# telemetry-phoenix.net
KiCad netlist of a schematic drawn in EAGLE
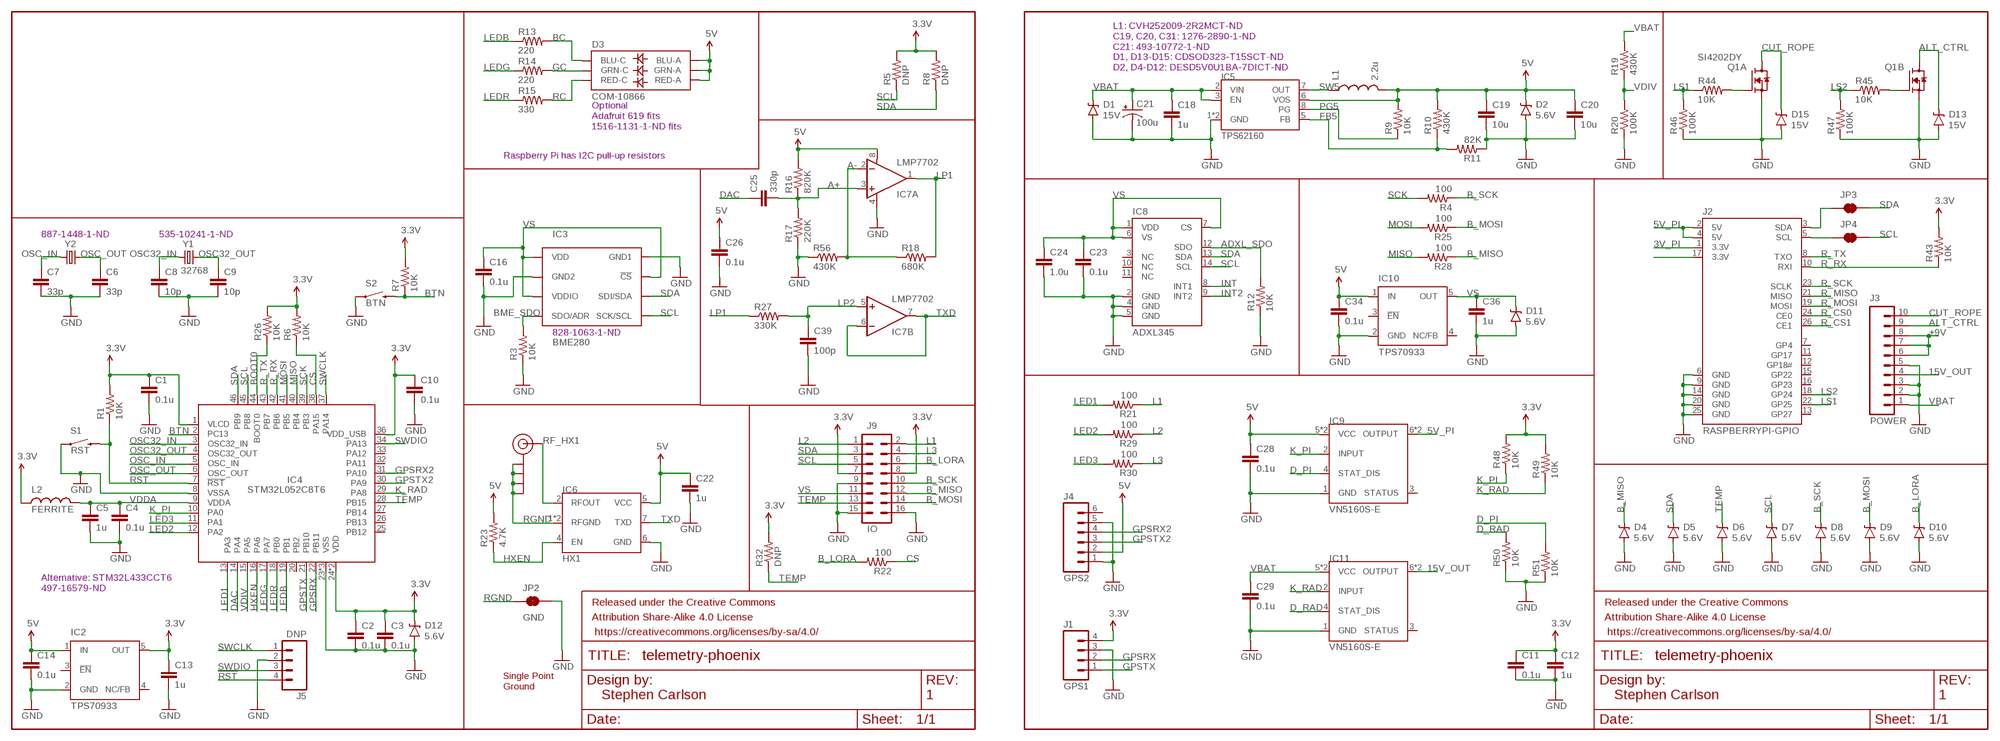
[diagram p0: schematic, sheet 1]

(export (version "E")
  (design (tool "Eeschema 10.0.6"))
  (components
    (comp (ref "C1")
      (value "0.1u")
      (footprint "eagle-import:0805")
      (libsource (lib "eagle-import") (part "CAP0805"))
    )
    (comp (ref "C2")
      (value "0.1u")
      (footprint "eagle-import:0805")
      (libsource (lib "eagle-import") (part "CAP0805"))
    )
    (comp (ref "C3")
      (value "0.1u")
      (footprint "eagle-import:0805")
      (libsource (lib "eagle-import") (part "CAP0805"))
    )
    (comp (ref "C4")
      (value "0.1u")
      (footprint "eagle-import:0805")
      (libsource (lib "eagle-import") (part "CAP0805"))
    )
    (comp (ref "C5")
      (value "1u")
      (footprint "eagle-import:0805")
      (libsource (lib "eagle-import") (part "CAP0805"))
    )
    (comp (ref "C6")
      (value "33p")
      (footprint "eagle-import:0805")
      (libsource (lib "eagle-import") (part "CAP0805"))
    )
    (comp (ref "C7")
      (value "33p")
      (footprint "eagle-import:0805")
      (libsource (lib "eagle-import") (part "CAP0805"))
    )
    (comp (ref "C8")
      (value "10p")
      (footprint "eagle-import:0805")
      (libsource (lib "eagle-import") (part "CAP0805"))
    )
    (comp (ref "C9")
      (value "10p")
      (footprint "eagle-import:0805")
      (libsource (lib "eagle-import") (part "CAP0805"))
    )
    (comp (ref "C10")
      (value "0.1u")
      (footprint "eagle-import:0805")
      (libsource (lib "eagle-import") (part "CAP0805"))
    )
    (comp (ref "C11")
      (value "0.1u")
      (footprint "eagle-import:0805")
      (libsource (lib "eagle-import") (part "CAP0805"))
    )
    (comp (ref "C12")
      (value "1u")
      (footprint "eagle-import:0805")
      (libsource (lib "eagle-import") (part "CAP0805"))
    )
    (comp (ref "C13")
      (value "1u")
      (footprint "eagle-import:0805")
      (libsource (lib "eagle-import") (part "CAP0805"))
    )
    (comp (ref "C14")
      (value "0.1u")
      (footprint "eagle-import:0805")
      (libsource (lib "eagle-import") (part "CAP0805"))
    )
    (comp (ref "C16")
      (value "0.1u")
      (footprint "eagle-import:0805")
      (libsource (lib "eagle-import") (part "CAP0805"))
    )
    (comp (ref "C18")
      (value "1u")
      (footprint "eagle-import:0805")
      (libsource (lib "eagle-import") (part "CAP0805"))
    )
    (comp (ref "C19")
      (value "10u")
      (footprint "eagle-import:0805")
      (libsource (lib "eagle-import") (part "CAP0805"))
    )
    (comp (ref "C20")
      (value "10u")
      (footprint "eagle-import:0805")
      (libsource (lib "eagle-import") (part "CAP0805"))
    )
    (comp (ref "C21")
      (value "100u")
      (footprint "eagle-import:PANASONIC_E")
      (libsource (lib "eagle-import") (part "CAP_POLE"))
    )
    (comp (ref "C22")
      (value "1u")
      (footprint "eagle-import:0805")
      (libsource (lib "eagle-import") (part "CAP0805"))
    )
    (comp (ref "C23")
      (value "0.1u")
      (footprint "eagle-import:0805")
      (libsource (lib "eagle-import") (part "CAP0805"))
    )
    (comp (ref "C24")
      (value "1.0u")
      (footprint "eagle-import:0805")
      (libsource (lib "eagle-import") (part "CAP0805"))
    )
    (comp (ref "C25")
      (value "330p")
      (footprint "eagle-import:0805")
      (libsource (lib "eagle-import") (part "CAP0805"))
    )
    (comp (ref "C26")
      (value "0.1u")
      (footprint "eagle-import:0805")
      (libsource (lib "eagle-import") (part "CAP0805"))
    )
    (comp (ref "C28")
      (value "0.1u")
      (footprint "eagle-import:0805")
      (libsource (lib "eagle-import") (part "CAP0805"))
    )
    (comp (ref "C29")
      (value "0.1u")
      (footprint "eagle-import:0805")
      (libsource (lib "eagle-import") (part "CAP0805"))
    )
    (comp (ref "C34")
      (value "0.1u")
      (footprint "eagle-import:0805")
      (libsource (lib "eagle-import") (part "CAP0805"))
    )
    (comp (ref "C36")
      (value "1u")
      (footprint "eagle-import:0805")
      (libsource (lib "eagle-import") (part "CAP0805"))
    )
    (comp (ref "C39")
      (value "100p")
      (footprint "eagle-import:0805")
      (libsource (lib "eagle-import") (part "CAP0805"))
    )
    (comp (ref "D1")
      (value "15V")
      (footprint "eagle-import:SOD-323")
      (libsource (lib "eagle-import") (part "DIODE-ZENER5.6V"))
    )
    (comp (ref "D2")
      (value "5.6V")
      (footprint "eagle-import:SOD-323")
      (libsource (lib "eagle-import") (part "DIODE-ZENER5.6V"))
    )
    (comp (ref "D3")
      (value "COM-10866")
      (footprint "eagle-import:LED-TRICOLOR-5050")
      (libsource (lib "eagle-import") (part "LED-TRICOLOR-5050NO_IC"))
    )
    (comp (ref "D4")
      (value "5.6V")
      (footprint "eagle-import:SOD-323")
      (libsource (lib "eagle-import") (part "DIODE-ZENER5.6V"))
    )
    (comp (ref "D5")
      (value "5.6V")
      (footprint "eagle-import:SOD-323")
      (libsource (lib "eagle-import") (part "DIODE-ZENER5.6V"))
    )
    (comp (ref "D6")
      (value "5.6V")
      (footprint "eagle-import:SOD-323")
      (libsource (lib "eagle-import") (part "DIODE-ZENER5.6V"))
    )
    (comp (ref "D7")
      (value "5.6V")
      (footprint "eagle-import:SOD-323")
      (libsource (lib "eagle-import") (part "DIODE-ZENER5.6V"))
    )
    (comp (ref "D8")
      (value "5.6V")
      (footprint "eagle-import:SOD-323")
      (libsource (lib "eagle-import") (part "DIODE-ZENER5.6V"))
    )
    (comp (ref "D9")
      (value "5.6V")
      (footprint "eagle-import:SOD-323")
      (libsource (lib "eagle-import") (part "DIODE-ZENER5.6V"))
    )
    (comp (ref "D10")
      (value "5.6V")
      (footprint "eagle-import:SOD-323")
      (libsource (lib "eagle-import") (part "DIODE-ZENER5.6V"))
    )
    (comp (ref "D11")
      (value "5.6V")
      (footprint "eagle-import:SOD-323")
      (libsource (lib "eagle-import") (part "DIODE-ZENER5.6V"))
    )
    (comp (ref "D12")
      (value "5.6V")
      (footprint "eagle-import:SOD-323")
      (libsource (lib "eagle-import") (part "DIODE-ZENER5.6V"))
    )
    (comp (ref "D13")
      (value "15V")
      (footprint "eagle-import:SOD-323")
      (libsource (lib "eagle-import") (part "DIODE-ZENER5.6V"))
    )
    (comp (ref "D15")
      (value "15V")
      (footprint "eagle-import:SOD-323")
      (libsource (lib "eagle-import") (part "DIODE-ZENER5.6V"))
    )
    (comp (ref "FRAME1")
      (value "FRAME-LETTERNO_PACKAGE")
      (footprint "eagle-import:DUMMY")
      (fields (field (name "DESIGNER") "Nobody"))
      (libsource (lib "eagle-import") (part "FRAME-LETTERNO_PACKAGE"))
    )
    (comp (ref "FRAME2")
      (value "FRAME-LETTERNO_PACKAGE")
      (footprint "eagle-import:DUMMY")
      (fields (field (name "DESIGNER") "Nobody"))
      (libsource (lib "eagle-import") (part "FRAME-LETTERNO_PACKAGE"))
    )
    (comp (ref "IC2")
      (value "TPS70933")
      (footprint "eagle-import:SOT23-DBV")
      (fields (field (name "MF") "TEXAS INSTRUMENTS") (field (name "MPN") "TPS77033DBVT"))
      (libsource (lib "eagle-import") (part "TPS77033"))
    )
    (comp (ref "IC3")
      (value "BME280")
      (footprint "eagle-import:BME280_LGA")
      (libsource (lib "eagle-import") (part "BME280"))
    )
    (comp (ref "IC4")
      (value "STM32L052C8T6")
      (footprint "eagle-import:TQFP48")
      (libsource (lib "eagle-import") (part "STM32L07C"))
    )
    (comp (ref "IC5")
      (value "TPS62160")
      (footprint "eagle-import:MSOP8")
      (libsource (lib "eagle-import") (part "TPS62160"))
    )
    (comp (ref "IC6")
      (value "HX1")
      (footprint "eagle-import:HX1")
      (libsource (lib "eagle-import") (part "HX1"))
    )
    (comp (ref "IC7")
      (value "LMP7702")
      (footprint "eagle-import:SO08")
      (libsource (lib "eagle-import") (part "OPAMP-DUALU"))
    )
    (comp (ref "IC8")
      (value "ADXL345")
      (footprint "eagle-import:LGA14")
      (libsource (lib "eagle-import") (part "ADXL345"))
    )
    (comp (ref "IC9")
      (value "VN5160S-E")
      (footprint "eagle-import:SO8")
      (libsource (lib "eagle-import") (part "VN5160S-E"))
    )
    (comp (ref "IC10")
      (value "TPS70933")
      (footprint "eagle-import:SOT23-DBV")
      (fields (field (name "MF") "TEXAS INSTRUMENTS") (field (name "MPN") "TPS77033DBVT"))
      (libsource (lib "eagle-import") (part "TPS77033"))
    )
    (comp (ref "IC11")
      (value "VN5160S-E")
      (footprint "eagle-import:SO8")
      (libsource (lib "eagle-import") (part "VN5160S-E"))
    )
    (comp (ref "J1")
      (value "GPS1")
      (footprint "eagle-import:1X04")
      (libsource (lib "eagle-import") (part "M04PTH"))
    )
    (comp (ref "J2")
      (value "RASPBERRYPI-GPIO")
      (footprint "eagle-import:2X13-PI")
      (libsource (lib "eagle-import") (part "RASPBERRYPI-GPIO"))
    )
    (comp (ref "J3")
      (value "POWER")
      (footprint "eagle-import:1X10_SCREW")
      (libsource (lib "eagle-import") (part "1X10"))
    )
    (comp (ref "J4")
      (value "GPS2")
      (footprint "eagle-import:1X06-1MM")
      (libsource (lib "eagle-import") (part "M06SMD-1MM"))
    )
    (comp (ref "J5")
      (value "DNP")
      (footprint "eagle-import:1X04_LOCK")
      (libsource (lib "eagle-import") (part "M04LOCK"))
    )
    (comp (ref "J6")
      (value "SMA_EDGE")
      (footprint "eagle-import:SMA-EDGE")
      (libsource (lib "eagle-import") (part "SMA_EDGE"))
    )
    (comp (ref "J9")
      (value "IO")
      (footprint "eagle-import:2X8")
      (libsource (lib "eagle-import") (part "M08X2"))
    )
    (comp (ref "JP2")
      (value "GND")
      (footprint "eagle-import:PAD-JUMPER-2-NC_BY_TRACE_YES_SILK")
      (libsource (lib "eagle-import") (part "JUMPER-PAD-2-NC_BY_TRACE"))
    )
    (comp (ref "JP3")
      (value "SDA")
      (footprint "eagle-import:PAD-JUMPER-2-NC_BY_TRACE_YES_SILK")
      (libsource (lib "eagle-import") (part "JUMPER-PAD-2-NC_BY_TRACE"))
    )
    (comp (ref "JP4")
      (value "SCL")
      (footprint "eagle-import:PAD-JUMPER-2-NC_BY_TRACE_YES_SILK")
      (libsource (lib "eagle-import") (part "JUMPER-PAD-2-NC_BY_TRACE"))
    )
    (comp (ref "L1")
      (value "2.2u")
      (footprint "eagle-import:1008")
      (libsource (lib "eagle-import") (part "INDUCTOR1008"))
    )
    (comp (ref "L2")
      (value "FERRITE")
      (footprint "eagle-import:1206")
      (libsource (lib "eagle-import") (part "INDUCTOR1206"))
    )
    (comp (ref "Q1")
      (value "SI4202DY")
      (footprint "eagle-import:SO8")
      (libsource (lib "eagle-import") (part "SI4202DY"))
    )
    (comp (ref "R1")
      (value "10K")
      (footprint "eagle-import:0805")
      (libsource (lib "eagle-import") (part "RESISTOR0805-RES"))
    )
    (comp (ref "R3")
      (value "10K")
      (footprint "eagle-import:0805")
      (libsource (lib "eagle-import") (part "RESISTOR0805-RES"))
    )
    (comp (ref "R4")
      (value "100")
      (footprint "eagle-import:0805")
      (libsource (lib "eagle-import") (part "RESISTOR0805-RES"))
    )
    (comp (ref "R5")
      (value "DNP")
      (footprint "eagle-import:0805")
      (libsource (lib "eagle-import") (part "RESISTOR0805-RES"))
    )
    (comp (ref "R6")
      (value "10K")
      (footprint "eagle-import:0805")
      (libsource (lib "eagle-import") (part "RESISTOR0805-RES"))
    )
    (comp (ref "R7")
      (value "10K")
      (footprint "eagle-import:0805")
      (libsource (lib "eagle-import") (part "RESISTOR0805-RES"))
    )
    (comp (ref "R8")
      (value "DNP")
      (footprint "eagle-import:0805")
      (libsource (lib "eagle-import") (part "RESISTOR0805-RES"))
    )
    (comp (ref "R9")
      (value "10K")
      (footprint "eagle-import:0805")
      (libsource (lib "eagle-import") (part "RESISTOR0805-RES"))
    )
    (comp (ref "R10")
      (value "430K")
      (footprint "eagle-import:0805")
      (libsource (lib "eagle-import") (part "RESISTOR0805-RES"))
    )
    (comp (ref "R11")
      (value "82K")
      (footprint "eagle-import:0805")
      (libsource (lib "eagle-import") (part "RESISTOR0805-RES"))
    )
    (comp (ref "R12")
      (value "10K")
      (footprint "eagle-import:0805")
      (libsource (lib "eagle-import") (part "RESISTOR0805-RES"))
    )
    (comp (ref "R13")
      (value "220")
      (footprint "eagle-import:0805")
      (libsource (lib "eagle-import") (part "RESISTOR0805-RES"))
    )
    (comp (ref "R14")
      (value "220")
      (footprint "eagle-import:0805")
      (libsource (lib "eagle-import") (part "RESISTOR0805-RES"))
    )
    (comp (ref "R15")
      (value "330")
      (footprint "eagle-import:0805")
      (libsource (lib "eagle-import") (part "RESISTOR0805-RES"))
    )
    (comp (ref "R16")
      (value "820K")
      (footprint "eagle-import:0805")
      (libsource (lib "eagle-import") (part "RESISTOR0805-RES"))
    )
    (comp (ref "R17")
      (value "220K")
      (footprint "eagle-import:0805")
      (libsource (lib "eagle-import") (part "RESISTOR0805-RES"))
    )
    (comp (ref "R18")
      (value "680K")
      (footprint "eagle-import:0805")
      (libsource (lib "eagle-import") (part "RESISTOR0805-RES"))
    )
    (comp (ref "R19")
      (value "430K")
      (footprint "eagle-import:0805")
      (libsource (lib "eagle-import") (part "RESISTOR0805-RES"))
    )
    (comp (ref "R20")
      (value "100K")
      (footprint "eagle-import:0805")
      (libsource (lib "eagle-import") (part "RESISTOR0805-RES"))
    )
    (comp (ref "R21")
      (value "100")
      (footprint "eagle-import:0805")
      (libsource (lib "eagle-import") (part "RESISTOR0805-RES"))
    )
    (comp (ref "R22")
      (value "100")
      (footprint "eagle-import:0805")
      (libsource (lib "eagle-import") (part "RESISTOR0805-RES"))
    )
    (comp (ref "R23")
      (value "4.7K")
      (footprint "eagle-import:0805")
      (libsource (lib "eagle-import") (part "RESISTOR0805-RES"))
    )
    (comp (ref "R25")
      (value "100")
      (footprint "eagle-import:0805")
      (libsource (lib "eagle-import") (part "RESISTOR0805-RES"))
    )
    (comp (ref "R26")
      (value "10K")
      (footprint "eagle-import:0805")
      (libsource (lib "eagle-import") (part "RESISTOR0805-RES"))
    )
    (comp (ref "R27")
      (value "330K")
      (footprint "eagle-import:0805")
      (libsource (lib "eagle-import") (part "RESISTOR0805-RES"))
    )
    (comp (ref "R28")
      (value "100")
      (footprint "eagle-import:0805")
      (libsource (lib "eagle-import") (part "RESISTOR0805-RES"))
    )
    (comp (ref "R29")
      (value "100")
      (footprint "eagle-import:0805")
      (libsource (lib "eagle-import") (part "RESISTOR0805-RES"))
    )
    (comp (ref "R30")
      (value "100")
      (footprint "eagle-import:0805")
      (libsource (lib "eagle-import") (part "RESISTOR0805-RES"))
    )
    (comp (ref "R32")
      (value "DNP")
      (footprint "eagle-import:0805")
      (libsource (lib "eagle-import") (part "RESISTOR0805-RES"))
    )
    (comp (ref "R43")
      (value "10K")
      (footprint "eagle-import:0805")
      (libsource (lib "eagle-import") (part "RESISTOR0805-RES"))
    )
    (comp (ref "R44")
      (value "10K")
      (footprint "eagle-import:0805")
      (libsource (lib "eagle-import") (part "RESISTOR0805-RES"))
    )
    (comp (ref "R45")
      (value "10K")
      (footprint "eagle-import:0805")
      (libsource (lib "eagle-import") (part "RESISTOR0805-RES"))
    )
    (comp (ref "R46")
      (value "100K")
      (footprint "eagle-import:0805")
      (libsource (lib "eagle-import") (part "RESISTOR0805-RES"))
    )
    (comp (ref "R47")
      (value "100K")
      (footprint "eagle-import:0805")
      (libsource (lib "eagle-import") (part "RESISTOR0805-RES"))
    )
    (comp (ref "R48")
      (value "10K")
      (footprint "eagle-import:0805")
      (libsource (lib "eagle-import") (part "RESISTOR0805-RES"))
    )
    (comp (ref "R49")
      (value "10K")
      (footprint "eagle-import:0805")
      (libsource (lib "eagle-import") (part "RESISTOR0805-RES"))
    )
    (comp (ref "R50")
      (value "10K")
      (footprint "eagle-import:0805")
      (libsource (lib "eagle-import") (part "RESISTOR0805-RES"))
    )
    (comp (ref "R51")
      (value "10K")
      (footprint "eagle-import:0805")
      (libsource (lib "eagle-import") (part "RESISTOR0805-RES"))
    )
    (comp (ref "R56")
      (value "430K")
      (footprint "eagle-import:0805")
      (libsource (lib "eagle-import") (part "RESISTOR0805-RES"))
    )
    (comp (ref "S1")
      (value "RST")
      (footprint "eagle-import:TACTILE-PTH-THIN")
      (libsource (lib "eagle-import") (part "SWITCH"))
    )
    (comp (ref "S2")
      (value "BTN")
      (footprint "eagle-import:TACTILE-PTH-THIN")
      (libsource (lib "eagle-import") (part "SWITCH"))
    )
    (comp (ref "Y1")
      (value "32768")
      (footprint "eagle-import:ABS25")
      (libsource (lib "eagle-import") (part "CRYSTAL"))
    )
    (comp (ref "Y2")
      (value "8M")
      (footprint "eagle-import:CRYSTAL-TXC-7A")
      (libsource (lib "eagle-import") (part "CRYSTALTXC-7A"))
    )
  )
  (nets
    (net (code "1") (name "/+9V") (class "Default")
      (node (ref "J3") (pin "6") (pinfunction "6_6") (pintype "passive"))
      (node (ref "J3") (pin "7") (pinfunction "7_7") (pintype "passive"))
      (node (ref "J3") (pin "8") (pinfunction "8_8") (pintype "passive"))
    )
    (net (code "2") (name "/3V_PI") (class "Default")
      (node (ref "J2") (pin "1") (pinfunction "3.3V_1") (pintype "power_in"))
    )
    (net (code "3") (name "/5V_PI") (class "Default")
      (node (ref "IC9") (pin "6") (pinfunction "OUTPUT_6") (pintype "passive"))
      (node (ref "IC9") (pin "7") (pinfunction "OUTPUT_7") (pintype "passive"))
      (node (ref "J2") (pin "2") (pinfunction "5V_2") (pintype "power_in"))
      (node (ref "J2") (pin "4") (pinfunction "5V_4") (pintype "power_in"))
    )
    (net (code "4") (name "/15V_OUT") (class "Default")
      (node (ref "IC11") (pin "6") (pinfunction "OUTPUT_6") (pintype "passive"))
      (node (ref "IC11") (pin "7") (pinfunction "OUTPUT_7") (pintype "passive"))
      (node (ref "J3") (pin "4") (pinfunction "4_4") (pintype "passive"))
    )
    (net (code "5") (name "/A+") (class "Default")
      (node (ref "C25") (pin "2") (pinfunction "2_2") (pintype "passive"))
      (node (ref "IC7") (pin "3") (pinfunction "+IN_3") (pintype "input"))
      (node (ref "R16") (pin "1") (pinfunction "1_1") (pintype "passive"))
      (node (ref "R17") (pin "2") (pinfunction "2_2") (pintype "passive"))
    )
    (net (code "6") (name "/A-") (class "Default")
      (node (ref "IC7") (pin "2") (pinfunction "-IN_2") (pintype "input"))
      (node (ref "R18") (pin "1") (pinfunction "1_1") (pintype "passive"))
      (node (ref "R56") (pin "2") (pinfunction "2_2") (pintype "passive"))
    )
    (net (code "7") (name "/ADXL_SDO") (class "Default")
      (node (ref "IC8") (pin "12") (pinfunction "SDO_12") (pintype "bidirectional"))
      (node (ref "R12") (pin "2") (pinfunction "2_2") (pintype "passive"))
    )
    (net (code "8") (name "/ALT_CTRL") (class "Default")
      (node (ref "D13") (pin "C") (pinfunction "C_C") (pintype "passive"))
      (node (ref "J3") (pin "9") (pinfunction "9_9") (pintype "passive"))
      (node (ref "Q1") (pin "5") (pinfunction "D_5") (pintype "passive"))
      (node (ref "Q1") (pin "6") (pinfunction "D_6") (pintype "passive"))
    )
    (net (code "9") (name "/BC") (class "Default")
      (node (ref "D3") (pin "4") (pinfunction "BLU-C_4") (pintype "bidirectional"))
      (node (ref "R13") (pin "2") (pinfunction "2_2") (pintype "passive"))
    )
    (net (code "10") (name "/BME_SDO") (class "Default")
      (node (ref "IC3") (pin "P$5") (pinfunction "SDO/ADR_P$5") (pintype "bidirectional"))
      (node (ref "R3") (pin "2") (pinfunction "2_2") (pintype "passive"))
    )
    (net (code "11") (name "/BOOT0") (class "Default")
      (node (ref "IC4") (pin "44") (pinfunction "BOOT0_44") (pintype "input"))
      (node (ref "R26") (pin "1") (pinfunction "1_1") (pintype "passive"))
    )
    (net (code "12") (name "/BTN") (class "Default")
      (node (ref "IC4") (pin "2") (pinfunction "PC13_2") (pintype "bidirectional"))
      (node (ref "R7") (pin "1") (pinfunction "1_1") (pintype "passive"))
      (node (ref "S2") (pin "2") (pinfunction "2_2") (pintype "passive"))
    )
    (net (code "13") (name "/B_LORA") (class "Default")
      (node (ref "D10") (pin "C") (pinfunction "C_C") (pintype "passive"))
      (node (ref "J9") (pin "6") (pinfunction "6_6") (pintype "passive"))
      (node (ref "R22") (pin "2") (pinfunction "2_2") (pintype "passive"))
    )
    (net (code "14") (name "/B_MISO") (class "Default")
      (node (ref "D4") (pin "C") (pinfunction "C_C") (pintype "passive"))
      (node (ref "J9") (pin "12") (pinfunction "12_12") (pintype "passive"))
      (node (ref "R28") (pin "1") (pinfunction "1_1") (pintype "passive"))
    )
    (net (code "15") (name "/B_MOSI") (class "Default")
      (node (ref "D9") (pin "C") (pinfunction "C_C") (pintype "passive"))
      (node (ref "J9") (pin "14") (pinfunction "14_14") (pintype "passive"))
      (node (ref "R25") (pin "1") (pinfunction "1_1") (pintype "passive"))
    )
    (net (code "16") (name "/B_SCK") (class "Default")
      (node (ref "D8") (pin "C") (pinfunction "C_C") (pintype "passive"))
      (node (ref "J9") (pin "10") (pinfunction "10_10") (pintype "passive"))
      (node (ref "R4") (pin "1") (pinfunction "1_1") (pintype "passive"))
    )
    (net (code "17") (name "/CS") (class "Default")
      (node (ref "IC4") (pin "38") (pinfunction "PA15_38") (pintype "bidirectional"))
      (node (ref "R22") (pin "1") (pinfunction "1_1") (pintype "passive"))
      (node (ref "R6") (pin "1") (pinfunction "1_1") (pintype "passive"))
    )
    (net (code "18") (name "/CUT_ROPE") (class "Default")
      (node (ref "D15") (pin "C") (pinfunction "C_C") (pintype "passive"))
      (node (ref "J3") (pin "10") (pinfunction "10_10") (pintype "passive"))
      (node (ref "Q1") (pin "7") (pinfunction "D_7") (pintype "passive"))
      (node (ref "Q1") (pin "8") (pinfunction "D_8") (pintype "passive"))
    )
    (net (code "19") (name "/DAC") (class "Default")
      (node (ref "C25") (pin "1") (pinfunction "1_1") (pintype "passive"))
      (node (ref "IC4") (pin "14") (pinfunction "PA4_14") (pintype "bidirectional"))
    )
    (net (code "20") (name "/D_PI") (class "Default")
      (node (ref "IC9") (pin "4") (pinfunction "STAT_DIS_4") (pintype "input"))
      (node (ref "R51") (pin "2") (pinfunction "2_2") (pintype "passive"))
    )
    (net (code "21") (name "/D_RAD") (class "Default")
      (node (ref "IC11") (pin "4") (pinfunction "STAT_DIS_4") (pintype "input"))
      (node (ref "R50") (pin "2") (pinfunction "2_2") (pintype "passive"))
    )
    (net (code "22") (name "/FB5") (class "Default")
      (node (ref "IC5") (pin "5") (pinfunction "FB_5") (pintype "input"))
      (node (ref "R10") (pin "1") (pinfunction "1_1") (pintype "passive"))
      (node (ref "R11") (pin "2") (pinfunction "2_2") (pintype "passive"))
    )
    (net (code "23") (name "/GC") (class "Default")
      (node (ref "D3") (pin "6") (pinfunction "GRN-C_6") (pintype "bidirectional"))
      (node (ref "R14") (pin "2") (pinfunction "2_2") (pintype "passive"))
    )
    (net (code "24") (name "/GPSRX") (class "Default")
      (node (ref "IC4") (pin "22") (pinfunction "PB11_22") (pintype "bidirectional"))
      (node (ref "J1") (pin "2") (pinfunction "2_2") (pintype "passive"))
    )
    (net (code "25") (name "/GPSRX2") (class "Default")
      (node (ref "IC4") (pin "31") (pinfunction "PA10_31") (pintype "bidirectional"))
      (node (ref "J4") (pin "4") (pinfunction "4_4") (pintype "passive"))
    )
    (net (code "26") (name "/GPSTX") (class "Default")
      (node (ref "IC4") (pin "21") (pinfunction "PB10_21") (pintype "bidirectional"))
      (node (ref "J1") (pin "1") (pinfunction "1_1") (pintype "passive"))
    )
    (net (code "27") (name "/GPSTX2") (class "Default")
      (node (ref "IC4") (pin "30") (pinfunction "PA9_30") (pintype "bidirectional"))
      (node (ref "J4") (pin "3") (pinfunction "3_3") (pintype "passive"))
    )
    (net (code "28") (name "/HXEN") (class "Default")
      (node (ref "IC4") (pin "16") (pinfunction "PA6_16") (pintype "bidirectional"))
      (node (ref "IC6") (pin "4") (pinfunction "EN_4") (pintype "input"))
      (node (ref "R23") (pin "1") (pinfunction "1_1") (pintype "passive"))
    )
    (net (code "29") (name "/INT") (class "Default")
      (node (ref "IC8") (pin "8") (pinfunction "INT1_8") (pintype "bidirectional"))
    )
    (net (code "30") (name "/INT2") (class "Default")
      (node (ref "IC8") (pin "9") (pinfunction "INT2_9") (pintype "bidirectional"))
    )
    (net (code "31") (name "/K_PI") (class "Default")
      (node (ref "IC4") (pin "10") (pinfunction "PA0_10") (pintype "bidirectional"))
      (node (ref "IC9") (pin "2") (pinfunction "INPUT_2") (pintype "input"))
      (node (ref "R48") (pin "1") (pinfunction "1_1") (pintype "passive"))
    )
    (net (code "32") (name "/K_RAD") (class "Default")
      (node (ref "IC11") (pin "2") (pinfunction "INPUT_2") (pintype "input"))
      (node (ref "IC4") (pin "29") (pinfunction "PA8_29") (pintype "bidirectional"))
      (node (ref "R49") (pin "1") (pinfunction "1_1") (pintype "passive"))
    )
    (net (code "33") (name "/L1") (class "Default")
      (node (ref "J9") (pin "2") (pinfunction "2_2") (pintype "passive"))
      (node (ref "R21") (pin "1") (pinfunction "1_1") (pintype "passive"))
    )
    (net (code "34") (name "/L2") (class "Default")
      (node (ref "J9") (pin "1") (pinfunction "1_1") (pintype "passive"))
      (node (ref "R29") (pin "1") (pinfunction "1_1") (pintype "passive"))
    )
    (net (code "35") (name "/L3") (class "Default")
      (node (ref "J9") (pin "4") (pinfunction "4_4") (pintype "passive"))
      (node (ref "R30") (pin "1") (pinfunction "1_1") (pintype "passive"))
    )
    (net (code "36") (name "/LED1") (class "Default")
      (node (ref "IC4") (pin "13") (pinfunction "PA3_13") (pintype "bidirectional"))
      (node (ref "R21") (pin "2") (pinfunction "2_2") (pintype "passive"))
    )
    (net (code "37") (name "/LED2") (class "Default")
      (node (ref "IC4") (pin "12") (pinfunction "PA2_12") (pintype "bidirectional"))
      (node (ref "R29") (pin "2") (pinfunction "2_2") (pintype "passive"))
    )
    (net (code "38") (name "/LED3") (class "Default")
      (node (ref "IC4") (pin "11") (pinfunction "PA1_11") (pintype "bidirectional"))
      (node (ref "R30") (pin "2") (pinfunction "2_2") (pintype "passive"))
    )
    (net (code "39") (name "/LEDB") (class "Default")
      (node (ref "IC4") (pin "19") (pinfunction "PB1_19") (pintype "bidirectional"))
      (node (ref "R13") (pin "1") (pinfunction "1_1") (pintype "passive"))
    )
    (net (code "40") (name "/LEDG") (class "Default")
      (node (ref "IC4") (pin "17") (pinfunction "PA7_17") (pintype "bidirectional"))
      (node (ref "R14") (pin "1") (pinfunction "1_1") (pintype "passive"))
    )
    (net (code "41") (name "/LEDR") (class "Default")
      (node (ref "IC4") (pin "18") (pinfunction "PB0_18") (pintype "bidirectional"))
      (node (ref "R15") (pin "1") (pinfunction "1_1") (pintype "passive"))
    )
    (net (code "42") (name "/LP1") (class "Default")
      (node (ref "IC7") (pin "1") (pinfunction "OUT_1") (pintype "output"))
      (node (ref "R18") (pin "2") (pinfunction "2_2") (pintype "passive"))
      (node (ref "R27") (pin "1") (pinfunction "1_1") (pintype "passive"))
    )
    (net (code "43") (name "/LP2") (class "Default")
      (node (ref "C39") (pin "1") (pinfunction "1_1") (pintype "passive"))
      (node (ref "IC7") (pin "5") (pinfunction "+IN_5") (pintype "input"))
      (node (ref "R27") (pin "2") (pinfunction "2_2") (pintype "passive"))
    )
    (net (code "44") (name "/LS1") (class "Default")
      (node (ref "J2") (pin "22") (pinfunction "GP25_22") (pintype "bidirectional"))
      (node (ref "R44") (pin "1") (pinfunction "1_1") (pintype "passive"))
      (node (ref "R46") (pin "2") (pinfunction "2_2") (pintype "passive"))
    )
    (net (code "45") (name "/LS2") (class "Default")
      (node (ref "J2") (pin "18") (pinfunction "GP24_18") (pintype "bidirectional"))
      (node (ref "R45") (pin "1") (pinfunction "1_1") (pintype "passive"))
      (node (ref "R47") (pin "2") (pinfunction "2_2") (pintype "passive"))
    )
    (net (code "46") (name "/MISO") (class "Default")
      (node (ref "IC4") (pin "40") (pinfunction "PB4_40") (pintype "bidirectional"))
      (node (ref "R28") (pin "2") (pinfunction "2_2") (pintype "passive"))
    )
    (net (code "47") (name "/MOSI") (class "Default")
      (node (ref "IC4") (pin "41") (pinfunction "PB5_41") (pintype "bidirectional"))
      (node (ref "R25") (pin "2") (pinfunction "2_2") (pintype "passive"))
    )
    (net (code "48") (name "/OSC32_IN") (class "Default")
      (node (ref "C8") (pin "1") (pinfunction "1_1") (pintype "passive"))
      (node (ref "IC4") (pin "3") (pinfunction "OSC32_IN_3") (pintype "bidirectional"))
      (node (ref "Y1") (pin "1") (pinfunction "1_1") (pintype "passive"))
    )
    (net (code "49") (name "/OSC32_OUT") (class "Default")
      (node (ref "C9") (pin "1") (pinfunction "1_1") (pintype "passive"))
      (node (ref "IC4") (pin "4") (pinfunction "OSC32_OUT_4") (pintype "bidirectional"))
      (node (ref "Y1") (pin "4") (pinfunction "2_4") (pintype "passive"))
    )
    (net (code "50") (name "/OSC_IN") (class "Default")
      (node (ref "C7") (pin "1") (pinfunction "1_1") (pintype "passive"))
      (node (ref "IC4") (pin "5") (pinfunction "OSC_IN_5") (pintype "bidirectional"))
      (node (ref "Y2") (pin "P$1") (pinfunction "1_P$1") (pintype "passive"))
    )
    (net (code "51") (name "/OSC_OUT") (class "Default")
      (node (ref "C6") (pin "1") (pinfunction "1_1") (pintype "passive"))
      (node (ref "IC4") (pin "6") (pinfunction "OSC_OUT_6") (pintype "bidirectional"))
      (node (ref "Y2") (pin "P$2") (pinfunction "2_P$2") (pintype "passive"))
    )
    (net (code "52") (name "/PG5") (class "Default")
      (node (ref "IC5") (pin "8") (pinfunction "PG_8") (pintype "open_collector"))
      (node (ref "R9") (pin "1") (pinfunction "1_1") (pintype "passive"))
    )
    (net (code "53") (name "/RC") (class "Default")
      (node (ref "D3") (pin "5") (pinfunction "RED-C_5") (pintype "bidirectional"))
      (node (ref "R15") (pin "2") (pinfunction "2_2") (pintype "passive"))
    )
    (net (code "54") (name "/RF_HX1") (class "Default")
      (node (ref "IC6") (pin "2") (pinfunction "RFOUT_2") (pintype "output"))
      (node (ref "J6") (pin "SIG") (pinfunction "SIGNAL_SIG") (pintype "bidirectional"))
    )
    (net (code "55") (name "/RGND") (class "Default")
      (node (ref "IC6") (pin "1") (pinfunction "RFGND_1") (pintype "power_in"))
      (node (ref "IC6") (pin "3") (pinfunction "RFGND_3") (pintype "power_in"))
      (node (ref "J6") (pin "GND@0") (pinfunction "GND_GND@0") (pintype "bidirectional"))
      (node (ref "J6") (pin "GND@1") (pinfunction "GND_GND@1") (pintype "bidirectional"))
      (node (ref "J6") (pin "GND@2") (pinfunction "GND_GND@2") (pintype "bidirectional"))
      (node (ref "J6") (pin "GND@3") (pinfunction "GND_GND@3") (pintype "bidirectional"))
      (node (ref "JP2") (pin "1") (pinfunction "1_1") (pintype "passive"))
    )
    (net (code "56") (name "/R_CS0") (class "Default")
      (node (ref "J2") (pin "24") (pinfunction "CE0_24") (pintype "output"))
    )
    (net (code "57") (name "/R_CS1") (class "Default")
      (node (ref "J2") (pin "26") (pinfunction "CE1_26") (pintype "output"))
    )
    (net (code "58") (name "/R_MISO") (class "Default")
      (node (ref "J2") (pin "21") (pinfunction "MISO_21") (pintype "input"))
    )
    (net (code "59") (name "/R_MOSI") (class "Default")
      (node (ref "J2") (pin "19") (pinfunction "MOSI_19") (pintype "output"))
    )
    (net (code "60") (name "/R_RX") (class "Default")
      (node (ref "IC4") (pin "42") (pinfunction "PB6_42") (pintype "bidirectional"))
      (node (ref "J2") (pin "10") (pinfunction "RXI_10") (pintype "input"))
      (node (ref "R43") (pin "1") (pinfunction "1_1") (pintype "passive"))
    )
    (net (code "61") (name "/R_SCK") (class "Default")
      (node (ref "J2") (pin "23") (pinfunction "SCLK_23") (pintype "output"))
    )
    (net (code "62") (name "/R_TX") (class "Default")
      (node (ref "IC4") (pin "43") (pinfunction "PB7_43") (pintype "bidirectional"))
      (node (ref "J2") (pin "8") (pinfunction "TXO_8") (pintype "output"))
    )
    (net (code "63") (name "/SCK") (class "Default")
      (node (ref "IC4") (pin "39") (pinfunction "PB3_39") (pintype "bidirectional"))
      (node (ref "R4") (pin "2") (pinfunction "2_2") (pintype "passive"))
    )
    (net (code "64") (name "/SCL") (class "Default")
      (node (ref "D7") (pin "C") (pinfunction "C_C") (pintype "passive"))
      (node (ref "IC3") (pin "P$4") (pinfunction "SCK/SCL_P$4") (pintype "bidirectional"))
      (node (ref "IC4") (pin "45") (pinfunction "PB8_45") (pintype "bidirectional"))
      (node (ref "IC8") (pin "14") (pinfunction "SCL_14") (pintype "bidirectional"))
      (node (ref "J9") (pin "5") (pinfunction "5_5") (pintype "passive"))
      (node (ref "JP4") (pin "2") (pinfunction "2_2") (pintype "passive"))
      (node (ref "R5") (pin "1") (pinfunction "1_1") (pintype "passive"))
    )
    (net (code "65") (name "/SDA") (class "Default")
      (node (ref "D5") (pin "C") (pinfunction "C_C") (pintype "passive"))
      (node (ref "IC3") (pin "P$3") (pinfunction "SDI/SDA_P$3") (pintype "bidirectional"))
      (node (ref "IC4") (pin "46") (pinfunction "PB9_46") (pintype "bidirectional"))
      (node (ref "IC8") (pin "13") (pinfunction "SDA_13") (pintype "bidirectional"))
      (node (ref "J9") (pin "3") (pinfunction "3_3") (pintype "passive"))
      (node (ref "JP3") (pin "2") (pinfunction "2_2") (pintype "passive"))
      (node (ref "R8") (pin "1") (pinfunction "1_1") (pintype "passive"))
    )
    (net (code "66") (name "/SW5") (class "Default")
      (node (ref "IC5") (pin "7") (pinfunction "OUT_7") (pintype "output"))
      (node (ref "L1") (pin "1") (pinfunction "1_1") (pintype "passive"))
    )
    (net (code "67") (name "/SWCLK") (class "Default")
      (node (ref "IC4") (pin "37") (pinfunction "PA14_37") (pintype "bidirectional"))
      (node (ref "J5") (pin "1") (pinfunction "1_1") (pintype "passive"))
    )
    (net (code "68") (name "/SWDIO") (class "Default")
      (node (ref "IC4") (pin "34") (pinfunction "PA13_34") (pintype "bidirectional"))
      (node (ref "J5") (pin "3") (pinfunction "3_3") (pintype "passive"))
    )
    (net (code "69") (name "/TEMP") (class "Default")
      (node (ref "D6") (pin "C") (pinfunction "C_C") (pintype "passive"))
      (node (ref "IC4") (pin "28") (pinfunction "PB15_28") (pintype "bidirectional"))
      (node (ref "J9") (pin "13") (pinfunction "13_13") (pintype "passive"))
      (node (ref "R32") (pin "1") (pinfunction "1_1") (pintype "passive"))
    )
    (net (code "70") (name "/TXD") (class "Default")
      (node (ref "IC6") (pin "7") (pinfunction "TXD_7") (pintype "input"))
      (node (ref "IC7") (pin "6") (pinfunction "-IN_6") (pintype "input"))
      (node (ref "IC7") (pin "7") (pinfunction "OUT_7") (pintype "output"))
    )
    (net (code "71") (name "/VBAT") (class "Default")
      (node (ref "C18") (pin "1") (pinfunction "1_1") (pintype "passive"))
      (node (ref "C21") (pin "+") (pinfunction "+_+") (pintype "passive"))
      (node (ref "C29") (pin "1") (pinfunction "1_1") (pintype "passive"))
      (node (ref "D1") (pin "C") (pinfunction "C_C") (pintype "passive"))
      (node (ref "IC11") (pin "5") (pinfunction "VCC_5") (pintype "power_in"))
      (node (ref "IC11") (pin "8") (pinfunction "VCC_8") (pintype "power_in"))
      (node (ref "IC5") (pin "2") (pinfunction "VIN_2") (pintype "power_in"))
      (node (ref "IC5") (pin "3") (pinfunction "EN_3") (pintype "input"))
      (node (ref "J3") (pin "1") (pinfunction "1_1") (pintype "passive"))
      (node (ref "R19") (pin "2") (pinfunction "2_2") (pintype "passive"))
    )
    (net (code "72") (name "/VDDA") (class "Default")
      (node (ref "C4") (pin "1") (pinfunction "1_1") (pintype "passive"))
      (node (ref "C5") (pin "1") (pinfunction "1_1") (pintype "passive"))
      (node (ref "IC4") (pin "9") (pinfunction "VDDA_9") (pintype "power_in"))
      (node (ref "L2") (pin "2") (pinfunction "2_2") (pintype "passive"))
    )
    (net (code "73") (name "/VDIV") (class "Default")
      (node (ref "IC4") (pin "15") (pinfunction "PA5_15") (pintype "bidirectional"))
      (node (ref "R19") (pin "1") (pinfunction "1_1") (pintype "passive"))
      (node (ref "R20") (pin "2") (pinfunction "2_2") (pintype "passive"))
    )
    (net (code "74") (name "/VS") (class "Default")
      (node (ref "C16") (pin "1") (pinfunction "1_1") (pintype "passive"))
      (node (ref "C23") (pin "1") (pinfunction "1_1") (pintype "passive"))
      (node (ref "C24") (pin "1") (pinfunction "1_1") (pintype "passive"))
      (node (ref "C36") (pin "1") (pinfunction "1_1") (pintype "passive"))
      (node (ref "D11") (pin "C") (pinfunction "C_C") (pintype "passive"))
      (node (ref "IC10") (pin "5") (pinfunction "OUT_5") (pintype "passive"))
      (node (ref "IC3") (pin "P$2") (pinfunction "~{CS}_P$2") (pintype "bidirectional"))
      (node (ref "IC3") (pin "P$6") (pinfunction "VDDIO_P$6") (pintype "bidirectional"))
      (node (ref "IC3") (pin "P$8") (pinfunction "VDD_P$8") (pintype "bidirectional"))
      (node (ref "IC8") (pin "1") (pinfunction "VDD_1") (pintype "bidirectional"))
      (node (ref "IC8") (pin "6") (pinfunction "VS_6") (pintype "bidirectional"))
      (node (ref "IC8") (pin "7") (pinfunction "CS_7") (pintype "bidirectional"))
      (node (ref "J9") (pin "11") (pinfunction "11_11") (pintype "passive"))
    )
    (net (code "75") (name "/~{RST}") (class "Default")
      (node (ref "IC4") (pin "7") (pinfunction "~{RST}_7") (pintype "input"))
      (node (ref "J5") (pin "4") (pinfunction "4_4") (pintype "passive"))
      (node (ref "R1") (pin "1") (pinfunction "1_1") (pintype "passive"))
      (node (ref "S1") (pin "2") (pinfunction "2_2") (pintype "passive"))
    )
    (net (code "76") (name "3.3V") (class "Default")
      (node (ref "C1") (pin "1") (pinfunction "1_1") (pintype "passive"))
      (node (ref "C10") (pin "1") (pinfunction "1_1") (pintype "passive"))
      (node (ref "C11") (pin "1") (pinfunction "1_1") (pintype "passive"))
      (node (ref "C12") (pin "1") (pinfunction "1_1") (pintype "passive"))
      (node (ref "C13") (pin "1") (pinfunction "1_1") (pintype "passive"))
      (node (ref "C2") (pin "1") (pinfunction "1_1") (pintype "passive"))
      (node (ref "C3") (pin "1") (pinfunction "1_1") (pintype "passive"))
      (node (ref "D12") (pin "C") (pinfunction "C_C") (pintype "passive"))
      (node (ref "IC2") (pin "5") (pinfunction "OUT_5") (pintype "passive"))
      (node (ref "IC4") (pin "1") (pinfunction "VLCD_1") (pintype "power_in"))
      (node (ref "IC4") (pin "24") (pinfunction "VDD_24") (pintype "power_in"))
      (node (ref "IC4") (pin "36") (pinfunction "VDD_USB_36") (pintype "power_in"))
      (node (ref "IC4") (pin "48") (pinfunction "VDD_48") (pintype "power_in"))
      (node (ref "J1") (pin "4") (pinfunction "4_4") (pintype "passive"))
      (node (ref "J9") (pin "7") (pinfunction "7_7") (pintype "passive"))
      (node (ref "J9") (pin "8") (pinfunction "8_8") (pintype "passive"))
      (node (ref "L2") (pin "1") (pinfunction "1_1") (pintype "passive"))
      (node (ref "R1") (pin "2") (pinfunction "2_2") (pintype "passive"))
      (node (ref "R26") (pin "2") (pinfunction "2_2") (pintype "passive"))
      (node (ref "R32") (pin "2") (pinfunction "2_2") (pintype "passive"))
      (node (ref "R43") (pin "2") (pinfunction "2_2") (pintype "passive"))
      (node (ref "R48") (pin "2") (pinfunction "2_2") (pintype "passive"))
      (node (ref "R49") (pin "2") (pinfunction "2_2") (pintype "passive"))
      (node (ref "R5") (pin "2") (pinfunction "2_2") (pintype "passive"))
      (node (ref "R6") (pin "2") (pinfunction "2_2") (pintype "passive"))
      (node (ref "R7") (pin "2") (pinfunction "2_2") (pintype "passive"))
      (node (ref "R8") (pin "2") (pinfunction "2_2") (pintype "passive"))
    )
    (net (code "77") (name "5V") (class "Default")
      (node (ref "C14") (pin "1") (pinfunction "1_1") (pintype "passive"))
      (node (ref "C19") (pin "1") (pinfunction "1_1") (pintype "passive"))
      (node (ref "C20") (pin "1") (pinfunction "1_1") (pintype "passive"))
      (node (ref "C22") (pin "1") (pinfunction "1_1") (pintype "passive"))
      (node (ref "C26") (pin "1") (pinfunction "1_1") (pintype "passive"))
      (node (ref "C28") (pin "1") (pinfunction "1_1") (pintype "passive"))
      (node (ref "C34") (pin "1") (pinfunction "1_1") (pintype "passive"))
      (node (ref "D2") (pin "C") (pinfunction "C_C") (pintype "passive"))
      (node (ref "D3") (pin "1") (pinfunction "GRN-A_1") (pintype "bidirectional"))
      (node (ref "D3") (pin "2") (pinfunction "RED-A_2") (pintype "bidirectional"))
      (node (ref "D3") (pin "3") (pinfunction "BLU-A_3") (pintype "bidirectional"))
      (node (ref "IC10") (pin "1") (pinfunction "IN_1") (pintype "input"))
      (node (ref "IC2") (pin "1") (pinfunction "IN_1") (pintype "input"))
      (node (ref "IC5") (pin "6") (pinfunction "VOS_6") (pintype "input"))
      (node (ref "IC6") (pin "5") (pinfunction "VCC_5") (pintype "power_in"))
      (node (ref "IC7") (pin "8") (pinfunction "V+_8") (pintype "power_in"))
      (node (ref "IC9") (pin "5") (pinfunction "VCC_5") (pintype "power_in"))
      (node (ref "IC9") (pin "8") (pinfunction "VCC_8") (pintype "power_in"))
      (node (ref "J4") (pin "2") (pinfunction "2_2") (pintype "passive"))
      (node (ref "L1") (pin "2") (pinfunction "2_2") (pintype "passive"))
      (node (ref "R10") (pin "2") (pinfunction "2_2") (pintype "passive"))
      (node (ref "R16") (pin "2") (pinfunction "2_2") (pintype "passive"))
      (node (ref "R23") (pin "2") (pinfunction "2_2") (pintype "passive"))
      (node (ref "R9") (pin "2") (pinfunction "2_2") (pintype "passive"))
    )
    (net (code "78") (name "GND") (class "Default")
      (node (ref "C1") (pin "2") (pinfunction "2_2") (pintype "passive"))
      (node (ref "C10") (pin "2") (pinfunction "2_2") (pintype "passive"))
      (node (ref "C11") (pin "2") (pinfunction "2_2") (pintype "passive"))
      (node (ref "C12") (pin "2") (pinfunction "2_2") (pintype "passive"))
      (node (ref "C13") (pin "2") (pinfunction "2_2") (pintype "passive"))
      (node (ref "C14") (pin "2") (pinfunction "2_2") (pintype "passive"))
      (node (ref "C16") (pin "2") (pinfunction "2_2") (pintype "passive"))
      (node (ref "C18") (pin "2") (pinfunction "2_2") (pintype "passive"))
      (node (ref "C19") (pin "2") (pinfunction "2_2") (pintype "passive"))
      (node (ref "C2") (pin "2") (pinfunction "2_2") (pintype "passive"))
      (node (ref "C20") (pin "2") (pinfunction "2_2") (pintype "passive"))
      (node (ref "C21") (pin "-") (pinfunction "-_-") (pintype "passive"))
      (node (ref "C22") (pin "2") (pinfunction "2_2") (pintype "passive"))
      (node (ref "C23") (pin "2") (pinfunction "2_2") (pintype "passive"))
      (node (ref "C24") (pin "2") (pinfunction "2_2") (pintype "passive"))
      (node (ref "C26") (pin "2") (pinfunction "2_2") (pintype "passive"))
      (node (ref "C28") (pin "2") (pinfunction "2_2") (pintype "passive"))
      (node (ref "C29") (pin "2") (pinfunction "2_2") (pintype "passive"))
      (node (ref "C3") (pin "2") (pinfunction "2_2") (pintype "passive"))
      (node (ref "C34") (pin "2") (pinfunction "2_2") (pintype "passive"))
      (node (ref "C36") (pin "2") (pinfunction "2_2") (pintype "passive"))
      (node (ref "C39") (pin "2") (pinfunction "2_2") (pintype "passive"))
      (node (ref "C4") (pin "2") (pinfunction "2_2") (pintype "passive"))
      (node (ref "C5") (pin "2") (pinfunction "2_2") (pintype "passive"))
      (node (ref "C6") (pin "2") (pinfunction "2_2") (pintype "passive"))
      (node (ref "C7") (pin "2") (pinfunction "2_2") (pintype "passive"))
      (node (ref "C8") (pin "2") (pinfunction "2_2") (pintype "passive"))
      (node (ref "C9") (pin "2") (pinfunction "2_2") (pintype "passive"))
      (node (ref "D1") (pin "A") (pinfunction "A_A") (pintype "passive"))
      (node (ref "D10") (pin "A") (pinfunction "A_A") (pintype "passive"))
      (node (ref "D11") (pin "A") (pinfunction "A_A") (pintype "passive"))
      (node (ref "D12") (pin "A") (pinfunction "A_A") (pintype "passive"))
      (node (ref "D13") (pin "A") (pinfunction "A_A") (pintype "passive"))
      (node (ref "D15") (pin "A") (pinfunction "A_A") (pintype "passive"))
      (node (ref "D2") (pin "A") (pinfunction "A_A") (pintype "passive"))
      (node (ref "D4") (pin "A") (pinfunction "A_A") (pintype "passive"))
      (node (ref "D5") (pin "A") (pinfunction "A_A") (pintype "passive"))
      (node (ref "D6") (pin "A") (pinfunction "A_A") (pintype "passive"))
      (node (ref "D7") (pin "A") (pinfunction "A_A") (pintype "passive"))
      (node (ref "D8") (pin "A") (pinfunction "A_A") (pintype "passive"))
      (node (ref "D9") (pin "A") (pinfunction "A_A") (pintype "passive"))
      (node (ref "IC10") (pin "2") (pinfunction "GND_2") (pintype "power_in"))
      (node (ref "IC11") (pin "1") (pinfunction "GND_1") (pintype "power_in"))
      (node (ref "IC2") (pin "2") (pinfunction "GND_2") (pintype "power_in"))
      (node (ref "IC3") (pin "P$1") (pinfunction "GND1_P$1") (pintype "bidirectional"))
      (node (ref "IC3") (pin "P$7") (pinfunction "GND2_P$7") (pintype "bidirectional"))
      (node (ref "IC4") (pin "23") (pinfunction "VSS_23") (pintype "power_in"))
      (node (ref "IC4") (pin "35") (pinfunction "VSS_35") (pintype "power_in"))
      (node (ref "IC4") (pin "47") (pinfunction "VSS_47") (pintype "power_in"))
      (node (ref "IC4") (pin "8") (pinfunction "VSSA_8") (pintype "power_in"))
      (node (ref "IC5") (pin "1") (pinfunction "GND_1") (pintype "power_in"))
      (node (ref "IC5") (pin "4") (pinfunction "GND_4") (pintype "power_in"))
      (node (ref "IC6") (pin "6") (pinfunction "GND_6") (pintype "power_in"))
      (node (ref "IC7") (pin "4") (pinfunction "V-_4") (pintype "power_in"))
      (node (ref "IC8") (pin "2") (pinfunction "GND_2") (pintype "bidirectional"))
      (node (ref "IC8") (pin "4") (pinfunction "GND_4") (pintype "bidirectional"))
      (node (ref "IC8") (pin "5") (pinfunction "GND_5") (pintype "bidirectional"))
      (node (ref "IC9") (pin "1") (pinfunction "GND_1") (pintype "power_in"))
      (node (ref "J1") (pin "3") (pinfunction "3_3") (pintype "passive"))
      (node (ref "J2") (pin "14") (pinfunction "GND_14") (pintype "power_in"))
      (node (ref "J2") (pin "20") (pinfunction "GND_20") (pintype "power_in"))
      (node (ref "J2") (pin "25") (pinfunction "GND_25") (pintype "power_in"))
      (node (ref "J2") (pin "6") (pinfunction "GND_6") (pintype "power_in"))
      (node (ref "J2") (pin "9") (pinfunction "GND_9") (pintype "power_in"))
      (node (ref "J3") (pin "2") (pinfunction "2_2") (pintype "passive"))
      (node (ref "J3") (pin "3") (pinfunction "3_3") (pintype "passive"))
      (node (ref "J3") (pin "5") (pinfunction "5_5") (pintype "passive"))
      (node (ref "J4") (pin "1") (pinfunction "1_1") (pintype "passive"))
      (node (ref "J4") (pin "5") (pinfunction "5_5") (pintype "passive"))
      (node (ref "J5") (pin "2") (pinfunction "2_2") (pintype "passive"))
      (node (ref "J9") (pin "15") (pinfunction "15_15") (pintype "passive"))
      (node (ref "J9") (pin "16") (pinfunction "16_16") (pintype "passive"))
      (node (ref "J9") (pin "9") (pinfunction "9_9") (pintype "passive"))
      (node (ref "JP2") (pin "2") (pinfunction "2_2") (pintype "passive"))
      (node (ref "Q1") (pin "1") (pinfunction "S_1") (pintype "passive"))
      (node (ref "Q1") (pin "3") (pinfunction "S_3") (pintype "passive"))
      (node (ref "R11") (pin "1") (pinfunction "1_1") (pintype "passive"))
      (node (ref "R12") (pin "1") (pinfunction "1_1") (pintype "passive"))
      (node (ref "R17") (pin "1") (pinfunction "1_1") (pintype "passive"))
      (node (ref "R20") (pin "1") (pinfunction "1_1") (pintype "passive"))
      (node (ref "R3") (pin "1") (pinfunction "1_1") (pintype "passive"))
      (node (ref "R46") (pin "1") (pinfunction "1_1") (pintype "passive"))
      (node (ref "R47") (pin "1") (pinfunction "1_1") (pintype "passive"))
      (node (ref "R50") (pin "1") (pinfunction "1_1") (pintype "passive"))
      (node (ref "R51") (pin "1") (pinfunction "1_1") (pintype "passive"))
      (node (ref "R56") (pin "1") (pinfunction "1_1") (pintype "passive"))
      (node (ref "S1") (pin "1") (pinfunction "1_1") (pintype "passive"))
      (node (ref "S2") (pin "1") (pinfunction "1_1") (pintype "passive"))
    )
    (net (code "79") (name "Net-(J2-SCL)") (class "Default")
      (node (ref "J2") (pin "5") (pinfunction "SCL_5") (pintype "bidirectional"))
      (node (ref "JP4") (pin "1") (pinfunction "1_1") (pintype "passive"))
    )
    (net (code "80") (name "Net-(J2-SDA)") (class "Default")
      (node (ref "J2") (pin "3") (pinfunction "SDA_3") (pintype "bidirectional"))
      (node (ref "JP3") (pin "1") (pinfunction "1_1") (pintype "passive"))
    )
    (net (code "81") (name "Net-(Q1A-G)") (class "Default")
      (node (ref "Q1") (pin "2") (pinfunction "G_2") (pintype "passive"))
      (node (ref "R44") (pin "2") (pinfunction "2_2") (pintype "passive"))
    )
    (net (code "82") (name "Net-(Q1B-G)") (class "Default")
      (node (ref "Q1") (pin "4") (pinfunction "G_4") (pintype "passive"))
      (node (ref "R45") (pin "2") (pinfunction "2_2") (pintype "passive"))
    )
    (net (code "83") (name "unconnected-(IC2-NC{slash}FB-Pad4)") (class "Default")
      (node (ref "IC2") (pin "4") (pinfunction "NC/FB_4") (pintype "passive"))
    )
    (net (code "84") (name "unconnected-(IC2-~{EN}-Pad3)") (class "Default")
      (node (ref "IC2") (pin "3") (pinfunction "~{EN}_3") (pintype "input"))
    )
    (net (code "85") (name "unconnected-(IC4-PA11-Pad32)") (class "Default")
      (node (ref "IC4") (pin "32") (pinfunction "PA11_32") (pintype "bidirectional"))
    )
    (net (code "86") (name "unconnected-(IC4-PA12-Pad33)") (class "Default")
      (node (ref "IC4") (pin "33") (pinfunction "PA12_33") (pintype "bidirectional"))
    )
    (net (code "87") (name "unconnected-(IC4-PB2-Pad20)") (class "Default")
      (node (ref "IC4") (pin "20") (pinfunction "PB2_20") (pintype "bidirectional"))
    )
    (net (code "88") (name "unconnected-(IC4-PB12-Pad25)") (class "Default")
      (node (ref "IC4") (pin "25") (pinfunction "PB12_25") (pintype "bidirectional"))
    )
    (net (code "89") (name "unconnected-(IC4-PB13-Pad26)") (class "Default")
      (node (ref "IC4") (pin "26") (pinfunction "PB13_26") (pintype "bidirectional"))
    )
    (net (code "90") (name "unconnected-(IC4-PB14-Pad27)") (class "Default")
      (node (ref "IC4") (pin "27") (pinfunction "PB14_27") (pintype "bidirectional"))
    )
    (net (code "91") (name "unconnected-(IC8-NC-Pad3)") (class "Default")
      (node (ref "IC8") (pin "3") (pinfunction "NC_3") (pintype "bidirectional"))
    )
    (net (code "92") (name "unconnected-(IC8-NC-Pad10)") (class "Default")
      (node (ref "IC8") (pin "10") (pinfunction "NC_10") (pintype "bidirectional"))
    )
    (net (code "93") (name "unconnected-(IC8-NC-Pad11)") (class "Default")
      (node (ref "IC8") (pin "11") (pinfunction "NC_11") (pintype "bidirectional"))
    )
    (net (code "94") (name "unconnected-(IC9-STATUS-Pad3)") (class "Default")
      (node (ref "IC9") (pin "3") (pinfunction "STATUS_3") (pintype "open_collector"))
    )
    (net (code "95") (name "unconnected-(IC10-NC{slash}FB-Pad4)") (class "Default")
      (node (ref "IC10") (pin "4") (pinfunction "NC/FB_4") (pintype "passive"))
    )
    (net (code "96") (name "unconnected-(IC10-~{EN}-Pad3)") (class "Default")
      (node (ref "IC10") (pin "3") (pinfunction "~{EN}_3") (pintype "input"))
    )
    (net (code "97") (name "unconnected-(IC11-STATUS-Pad3)") (class "Default")
      (node (ref "IC11") (pin "3") (pinfunction "STATUS_3") (pintype "open_collector"))
    )
    (net (code "98") (name "unconnected-(J2-3.3V-Pad17)") (class "Default")
      (node (ref "J2") (pin "17") (pinfunction "3.3V_17") (pintype "power_in"))
    )
    (net (code "99") (name "unconnected-(J2-GP4-Pad7)") (class "Default")
      (node (ref "J2") (pin "7") (pinfunction "GP4_7") (pintype "bidirectional"))
    )
    (net (code "100") (name "unconnected-(J2-GP17-Pad11)") (class "Default")
      (node (ref "J2") (pin "11") (pinfunction "GP17_11") (pintype "bidirectional"))
    )
    (net (code "101") (name "unconnected-(J2-GP18#-Pad12)") (class "Default")
      (node (ref "J2") (pin "12") (pinfunction "GP18#_12") (pintype "bidirectional"))
    )
    (net (code "102") (name "unconnected-(J2-GP22-Pad15)") (class "Default")
      (node (ref "J2") (pin "15") (pinfunction "GP22_15") (pintype "bidirectional"))
    )
    (net (code "103") (name "unconnected-(J2-GP23-Pad16)") (class "Default")
      (node (ref "J2") (pin "16") (pinfunction "GP23_16") (pintype "bidirectional"))
    )
    (net (code "104") (name "unconnected-(J2-GP27-Pad13)") (class "Default")
      (node (ref "J2") (pin "13") (pinfunction "GP27_13") (pintype "bidirectional"))
    )
    (net (code "105") (name "unconnected-(J4-Pad6)") (class "Default")
      (node (ref "J4") (pin "6") (pinfunction "6_6") (pintype "passive"))
    )
  )
)
